# DBoard_conn.net
KiCad netlist of a schematic drawn in Altium Designer
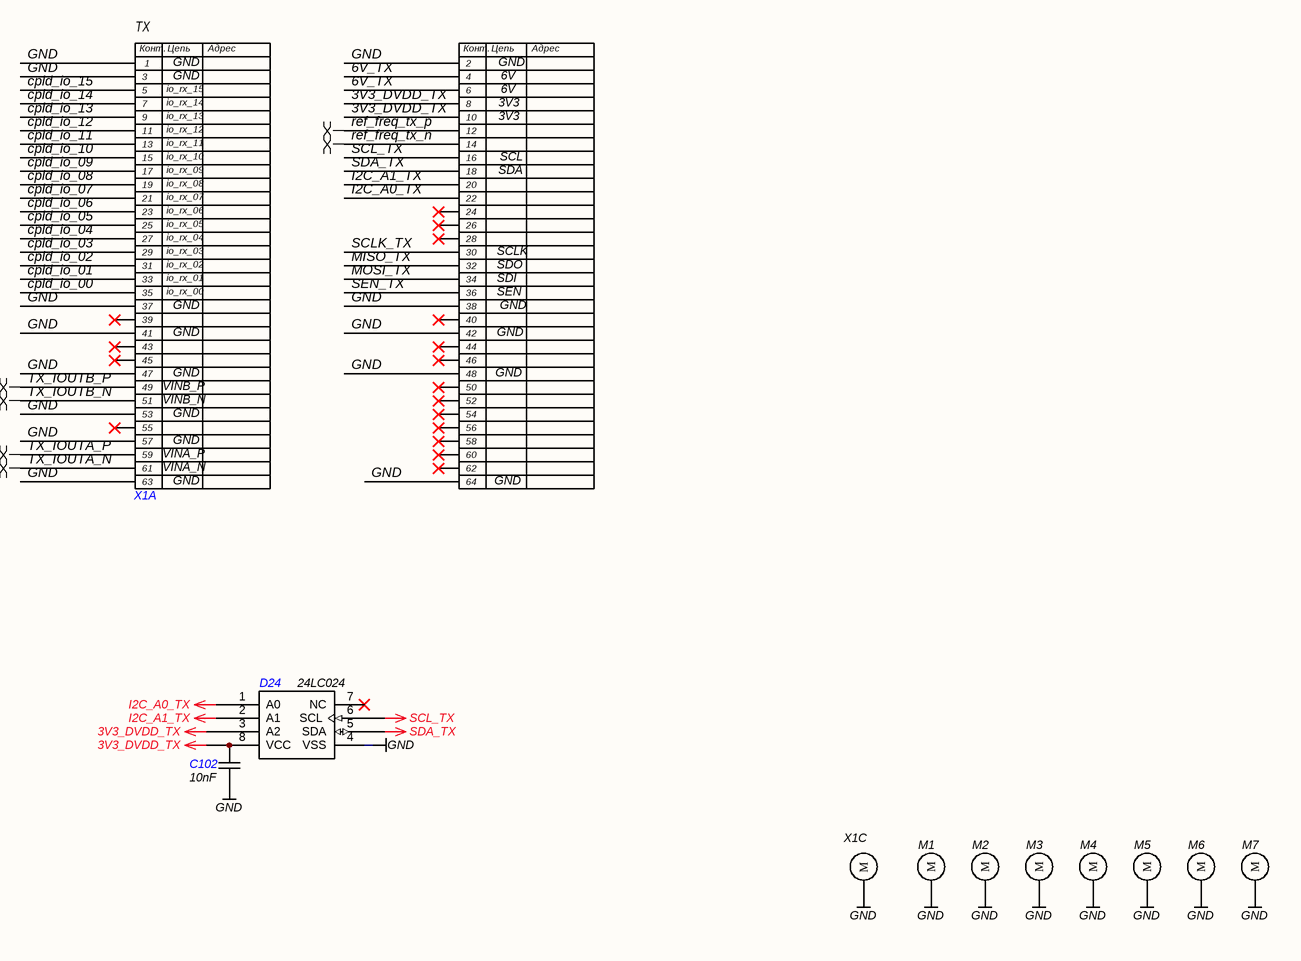
[diagram p0: DBoard_conn.SchDoc]

(export (version "E")
  (design (tool "Eeschema 10.0.6"))
  (components
    (comp (ref "C102")
      (value "10nF")
      (footprint "C0402")
      (description "SMD Capacitor")
      (fields (field (name "MANUFACTURER") "Murata") (field (name "TOLERANCE") "10%"))
      (libsource (lib "Kintex_SDR") (part "CAP"))
    )
    (comp (ref "D24")
      (value "24LC024")
      (footprint "SOIC_SN8")
      (description "I2C EEPROM")
      (fields (field (name "MANUFACTURER") "Microchip") (field (name "VOLTAGE") "2.5-5.5V"))
      (libsource (lib "Kintex_SDR") (part "24LC024"))
    )
    (comp (ref "M1")
      (value "Via")
      (footprint "Mechanical_Via_2.6x4.2")
      (description "Mechanical Via")
      (libsource (lib "Kintex_SDR") (part "Mechanical Via"))
    )
    (comp (ref "M2")
      (value "Via")
      (footprint "Mechanical_Via_2.6x4.2")
      (description "Mechanical Via")
      (libsource (lib "Kintex_SDR") (part "Mechanical Via"))
    )
    (comp (ref "M3")
      (value "Via")
      (footprint "Mechanical_Via_2.6x4.2")
      (description "Mechanical Via")
      (libsource (lib "Kintex_SDR") (part "Mechanical Via"))
    )
    (comp (ref "M4")
      (value "Via")
      (footprint "Mechanical_Via_2.6x4.2")
      (description "Mechanical Via")
      (libsource (lib "Kintex_SDR") (part "Mechanical Via"))
    )
    (comp (ref "M5")
      (value "Via")
      (footprint "Mechanical_Via_2.6x4.2")
      (description "Mechanical Via")
      (libsource (lib "Kintex_SDR") (part "Mechanical Via"))
    )
    (comp (ref "M6")
      (value "Via")
      (footprint "Mechanical_Via_2.6x4.2")
      (description "Mechanical Via")
      (libsource (lib "Kintex_SDR") (part "Mechanical Via"))
    )
    (comp (ref "M7")
      (value "Via")
      (footprint "Mechanical_Via_2.6x4.2")
      (description "Mechanical Via")
      (libsource (lib "Kintex_SDR") (part "Mechanical Via"))
    )
    (comp (ref "X1")
      (value "DBoard")
      (footprint "DBLib:DBOARD-HALF-TX-MB")
      (description "USRP DBoard")
      (fields (field (name "MANUFACTURER") "Molex"))
      (libsource (lib "DBLib") (part "DBoard"))
    )
  )
  (nets
    (net (code "1") (name "/6V_TX") (class "Default")
      (node (ref "X1") (pin "4") (pinfunction "4_4") (pintype "passive"))
      (node (ref "X1") (pin "6") (pinfunction "6_6") (pintype "passive"))
    )
    (net (code "2") (name "/MISO_TX") (class "Default")
      (node (ref "X1") (pin "32") (pinfunction "32_32") (pintype "passive"))
    )
    (net (code "3") (name "/MOSI_TX") (class "Default")
      (node (ref "X1") (pin "34") (pinfunction "34_34") (pintype "passive"))
    )
    (net (code "4") (name "/SCLK_TX") (class "Default")
      (node (ref "X1") (pin "30") (pinfunction "30_30") (pintype "passive"))
    )
    (net (code "5") (name "/SEN_TX") (class "Default")
      (node (ref "X1") (pin "36") (pinfunction "36_36") (pintype "passive"))
    )
    (net (code "6") (name "/TX_IOUTA_N") (class "Default")
      (node (ref "X1") (pin "61") (pinfunction "61_61") (pintype "passive"))
    )
    (net (code "7") (name "/TX_IOUTA_P") (class "Default")
      (node (ref "X1") (pin "59") (pinfunction "59_59") (pintype "passive"))
    )
    (net (code "8") (name "/TX_IOUTB_N") (class "Default")
      (node (ref "X1") (pin "51") (pinfunction "51_51") (pintype "passive"))
    )
    (net (code "9") (name "/TX_IOUTB_P") (class "Default")
      (node (ref "X1") (pin "49") (pinfunction "49_49") (pintype "passive"))
    )
    (net (code "10") (name "/cpld_io_00") (class "Default")
      (node (ref "X1") (pin "35") (pinfunction "35_35") (pintype "passive"))
    )
    (net (code "11") (name "/cpld_io_01") (class "Default")
      (node (ref "X1") (pin "33") (pinfunction "33_33") (pintype "passive"))
    )
    (net (code "12") (name "/cpld_io_02") (class "Default")
      (node (ref "X1") (pin "31") (pinfunction "31_31") (pintype "passive"))
    )
    (net (code "13") (name "/cpld_io_03") (class "Default")
      (node (ref "X1") (pin "29") (pinfunction "29_29") (pintype "passive"))
    )
    (net (code "14") (name "/cpld_io_04") (class "Default")
      (node (ref "X1") (pin "27") (pinfunction "27_27") (pintype "passive"))
    )
    (net (code "15") (name "/cpld_io_05") (class "Default")
      (node (ref "X1") (pin "25") (pinfunction "25_25") (pintype "passive"))
    )
    (net (code "16") (name "/cpld_io_06") (class "Default")
      (node (ref "X1") (pin "23") (pinfunction "23_23") (pintype "passive"))
    )
    (net (code "17") (name "/cpld_io_07") (class "Default")
      (node (ref "X1") (pin "21") (pinfunction "21_21") (pintype "passive"))
    )
    (net (code "18") (name "/cpld_io_08") (class "Default")
      (node (ref "X1") (pin "19") (pinfunction "19_19") (pintype "passive"))
    )
    (net (code "19") (name "/cpld_io_09") (class "Default")
      (node (ref "X1") (pin "17") (pinfunction "17_17") (pintype "passive"))
    )
    (net (code "20") (name "/cpld_io_10") (class "Default")
      (node (ref "X1") (pin "15") (pinfunction "15_15") (pintype "passive"))
    )
    (net (code "21") (name "/cpld_io_11") (class "Default")
      (node (ref "X1") (pin "13") (pinfunction "13_13") (pintype "passive"))
    )
    (net (code "22") (name "/cpld_io_12") (class "Default")
      (node (ref "X1") (pin "11") (pinfunction "11_11") (pintype "passive"))
    )
    (net (code "23") (name "/cpld_io_13") (class "Default")
      (node (ref "X1") (pin "9") (pinfunction "9_9") (pintype "passive"))
    )
    (net (code "24") (name "/cpld_io_14") (class "Default")
      (node (ref "X1") (pin "7") (pinfunction "7_7") (pintype "passive"))
    )
    (net (code "25") (name "/cpld_io_15") (class "Default")
      (node (ref "X1") (pin "5") (pinfunction "5_5") (pintype "passive"))
    )
    (net (code "26") (name "/ref_freq_tx_n") (class "Default")
      (node (ref "X1") (pin "14") (pinfunction "14_14") (pintype "passive"))
    )
    (net (code "27") (name "/ref_freq_tx_p") (class "Default")
      (node (ref "X1") (pin "12") (pinfunction "12_12") (pintype "passive"))
    )
    (net (code "28") (name "3V3_DVDD_TX") (class "Default")
      (node (ref "C102") (pin "2") (pinfunction "2_2") (pintype "passive"))
      (node (ref "D24") (pin "3") (pinfunction "A2_3") (pintype "passive"))
      (node (ref "D24") (pin "8") (pinfunction "VCC_8") (pintype "power_in"))
      (node (ref "X1") (pin "10") (pinfunction "10_10") (pintype "passive"))
      (node (ref "X1") (pin "8") (pinfunction "8_8") (pintype "passive"))
    )
    (net (code "29") (name "GND") (class "Default")
      (node (ref "C102") (pin "1") (pinfunction "1_1") (pintype "passive"))
      (node (ref "D24") (pin "4") (pinfunction "VSS_4") (pintype "power_in"))
      (node (ref "M1") (pin "0") (pinfunction "M_0") (pintype "passive"))
      (node (ref "M2") (pin "0") (pinfunction "M_0") (pintype "passive"))
      (node (ref "M3") (pin "0") (pinfunction "M_0") (pintype "passive"))
      (node (ref "M4") (pin "0") (pinfunction "M_0") (pintype "passive"))
      (node (ref "M5") (pin "0") (pinfunction "M_0") (pintype "passive"))
      (node (ref "M6") (pin "0") (pinfunction "M_0") (pintype "passive"))
      (node (ref "M7") (pin "0") (pinfunction "M_0") (pintype "passive"))
      (node (ref "X1") (pin "0") (pinfunction "M_0") (pintype "passive"))
      (node (ref "X1") (pin "1") (pinfunction "1_1") (pintype "passive"))
      (node (ref "X1") (pin "2") (pinfunction "2_2") (pintype "passive"))
      (node (ref "X1") (pin "3") (pinfunction "3_3") (pintype "passive"))
      (node (ref "X1") (pin "37") (pinfunction "37_37") (pintype "passive"))
      (node (ref "X1") (pin "38") (pinfunction "38_38") (pintype "passive"))
      (node (ref "X1") (pin "41") (pinfunction "41_41") (pintype "passive"))
      (node (ref "X1") (pin "42") (pinfunction "42_42") (pintype "passive"))
      (node (ref "X1") (pin "47") (pinfunction "47_47") (pintype "passive"))
      (node (ref "X1") (pin "48") (pinfunction "48_48") (pintype "passive"))
      (node (ref "X1") (pin "53") (pinfunction "53_53") (pintype "passive"))
      (node (ref "X1") (pin "57") (pinfunction "57_57") (pintype "passive"))
      (node (ref "X1") (pin "63") (pinfunction "63_63") (pintype "passive"))
      (node (ref "X1") (pin "64") (pinfunction "64_64") (pintype "passive"))
    )
    (net (code "30") (name "I2C_A0_TX") (class "Default")
      (node (ref "D24") (pin "1") (pinfunction "A0_1") (pintype "passive"))
      (node (ref "X1") (pin "22") (pinfunction "22_22") (pintype "passive"))
    )
    (net (code "31") (name "I2C_A1_TX") (class "Default")
      (node (ref "D24") (pin "2") (pinfunction "A1_2") (pintype "passive"))
      (node (ref "X1") (pin "20") (pinfunction "20_20") (pintype "passive"))
    )
    (net (code "32") (name "SCL_TX") (class "Default")
      (node (ref "D24") (pin "6") (pinfunction "SCL_6") (pintype "input"))
      (node (ref "X1") (pin "16") (pinfunction "16_16") (pintype "passive"))
    )
    (net (code "33") (name "SDA_TX") (class "Default")
      (node (ref "D24") (pin "5") (pinfunction "SDA_5") (pintype "bidirectional"))
      (node (ref "X1") (pin "18") (pinfunction "18_18") (pintype "passive"))
    )
    (net (code "34") (name "unconnected-(D24-NC-Pad7)") (class "Default")
      (node (ref "D24") (pin "7") (pinfunction "NC_7") (pintype "passive+no_connect"))
    )
    (net (code "35") (name "unconnected-(X1-Pad24)") (class "Default")
      (node (ref "X1") (pin "24") (pinfunction "24_24") (pintype "passive+no_connect"))
    )
    (net (code "36") (name "unconnected-(X1-Pad26)") (class "Default")
      (node (ref "X1") (pin "26") (pinfunction "26_26") (pintype "passive+no_connect"))
    )
    (net (code "37") (name "unconnected-(X1-Pad28)") (class "Default")
      (node (ref "X1") (pin "28") (pinfunction "28_28") (pintype "passive+no_connect"))
    )
    (net (code "38") (name "unconnected-(X1-Pad39)") (class "Default")
      (node (ref "X1") (pin "39") (pinfunction "39_39") (pintype "passive+no_connect"))
    )
    (net (code "39") (name "unconnected-(X1-Pad40)") (class "Default")
      (node (ref "X1") (pin "40") (pinfunction "40_40") (pintype "passive+no_connect"))
    )
    (net (code "40") (name "unconnected-(X1-Pad43)") (class "Default")
      (node (ref "X1") (pin "43") (pinfunction "43_43") (pintype "passive+no_connect"))
    )
    (net (code "41") (name "unconnected-(X1-Pad44)") (class "Default")
      (node (ref "X1") (pin "44") (pinfunction "44_44") (pintype "passive+no_connect"))
    )
    (net (code "42") (name "unconnected-(X1-Pad45)") (class "Default")
      (node (ref "X1") (pin "45") (pinfunction "45_45") (pintype "passive+no_connect"))
    )
    (net (code "43") (name "unconnected-(X1-Pad46)") (class "Default")
      (node (ref "X1") (pin "46") (pinfunction "46_46") (pintype "passive+no_connect"))
    )
    (net (code "44") (name "unconnected-(X1-Pad50)") (class "Default")
      (node (ref "X1") (pin "50") (pinfunction "50_50") (pintype "passive+no_connect"))
    )
    (net (code "45") (name "unconnected-(X1-Pad52)") (class "Default")
      (node (ref "X1") (pin "52") (pinfunction "52_52") (pintype "passive+no_connect"))
    )
    (net (code "46") (name "unconnected-(X1-Pad54)") (class "Default")
      (node (ref "X1") (pin "54") (pinfunction "54_54") (pintype "passive+no_connect"))
    )
    (net (code "47") (name "unconnected-(X1-Pad55)") (class "Default")
      (node (ref "X1") (pin "55") (pinfunction "55_55") (pintype "passive+no_connect"))
    )
    (net (code "48") (name "unconnected-(X1-Pad56)") (class "Default")
      (node (ref "X1") (pin "56") (pinfunction "56_56") (pintype "passive+no_connect"))
    )
    (net (code "49") (name "unconnected-(X1-Pad58)") (class "Default")
      (node (ref "X1") (pin "58") (pinfunction "58_58") (pintype "passive+no_connect"))
    )
    (net (code "50") (name "unconnected-(X1-Pad60)") (class "Default")
      (node (ref "X1") (pin "60") (pinfunction "60_60") (pintype "passive+no_connect"))
    )
    (net (code "51") (name "unconnected-(X1-Pad62)") (class "Default")
      (node (ref "X1") (pin "62") (pinfunction "62_62") (pintype "passive+no_connect"))
    )
  )
)
